# design.net
KiCad netlist of a schematic drawn in EasyEDA Pro
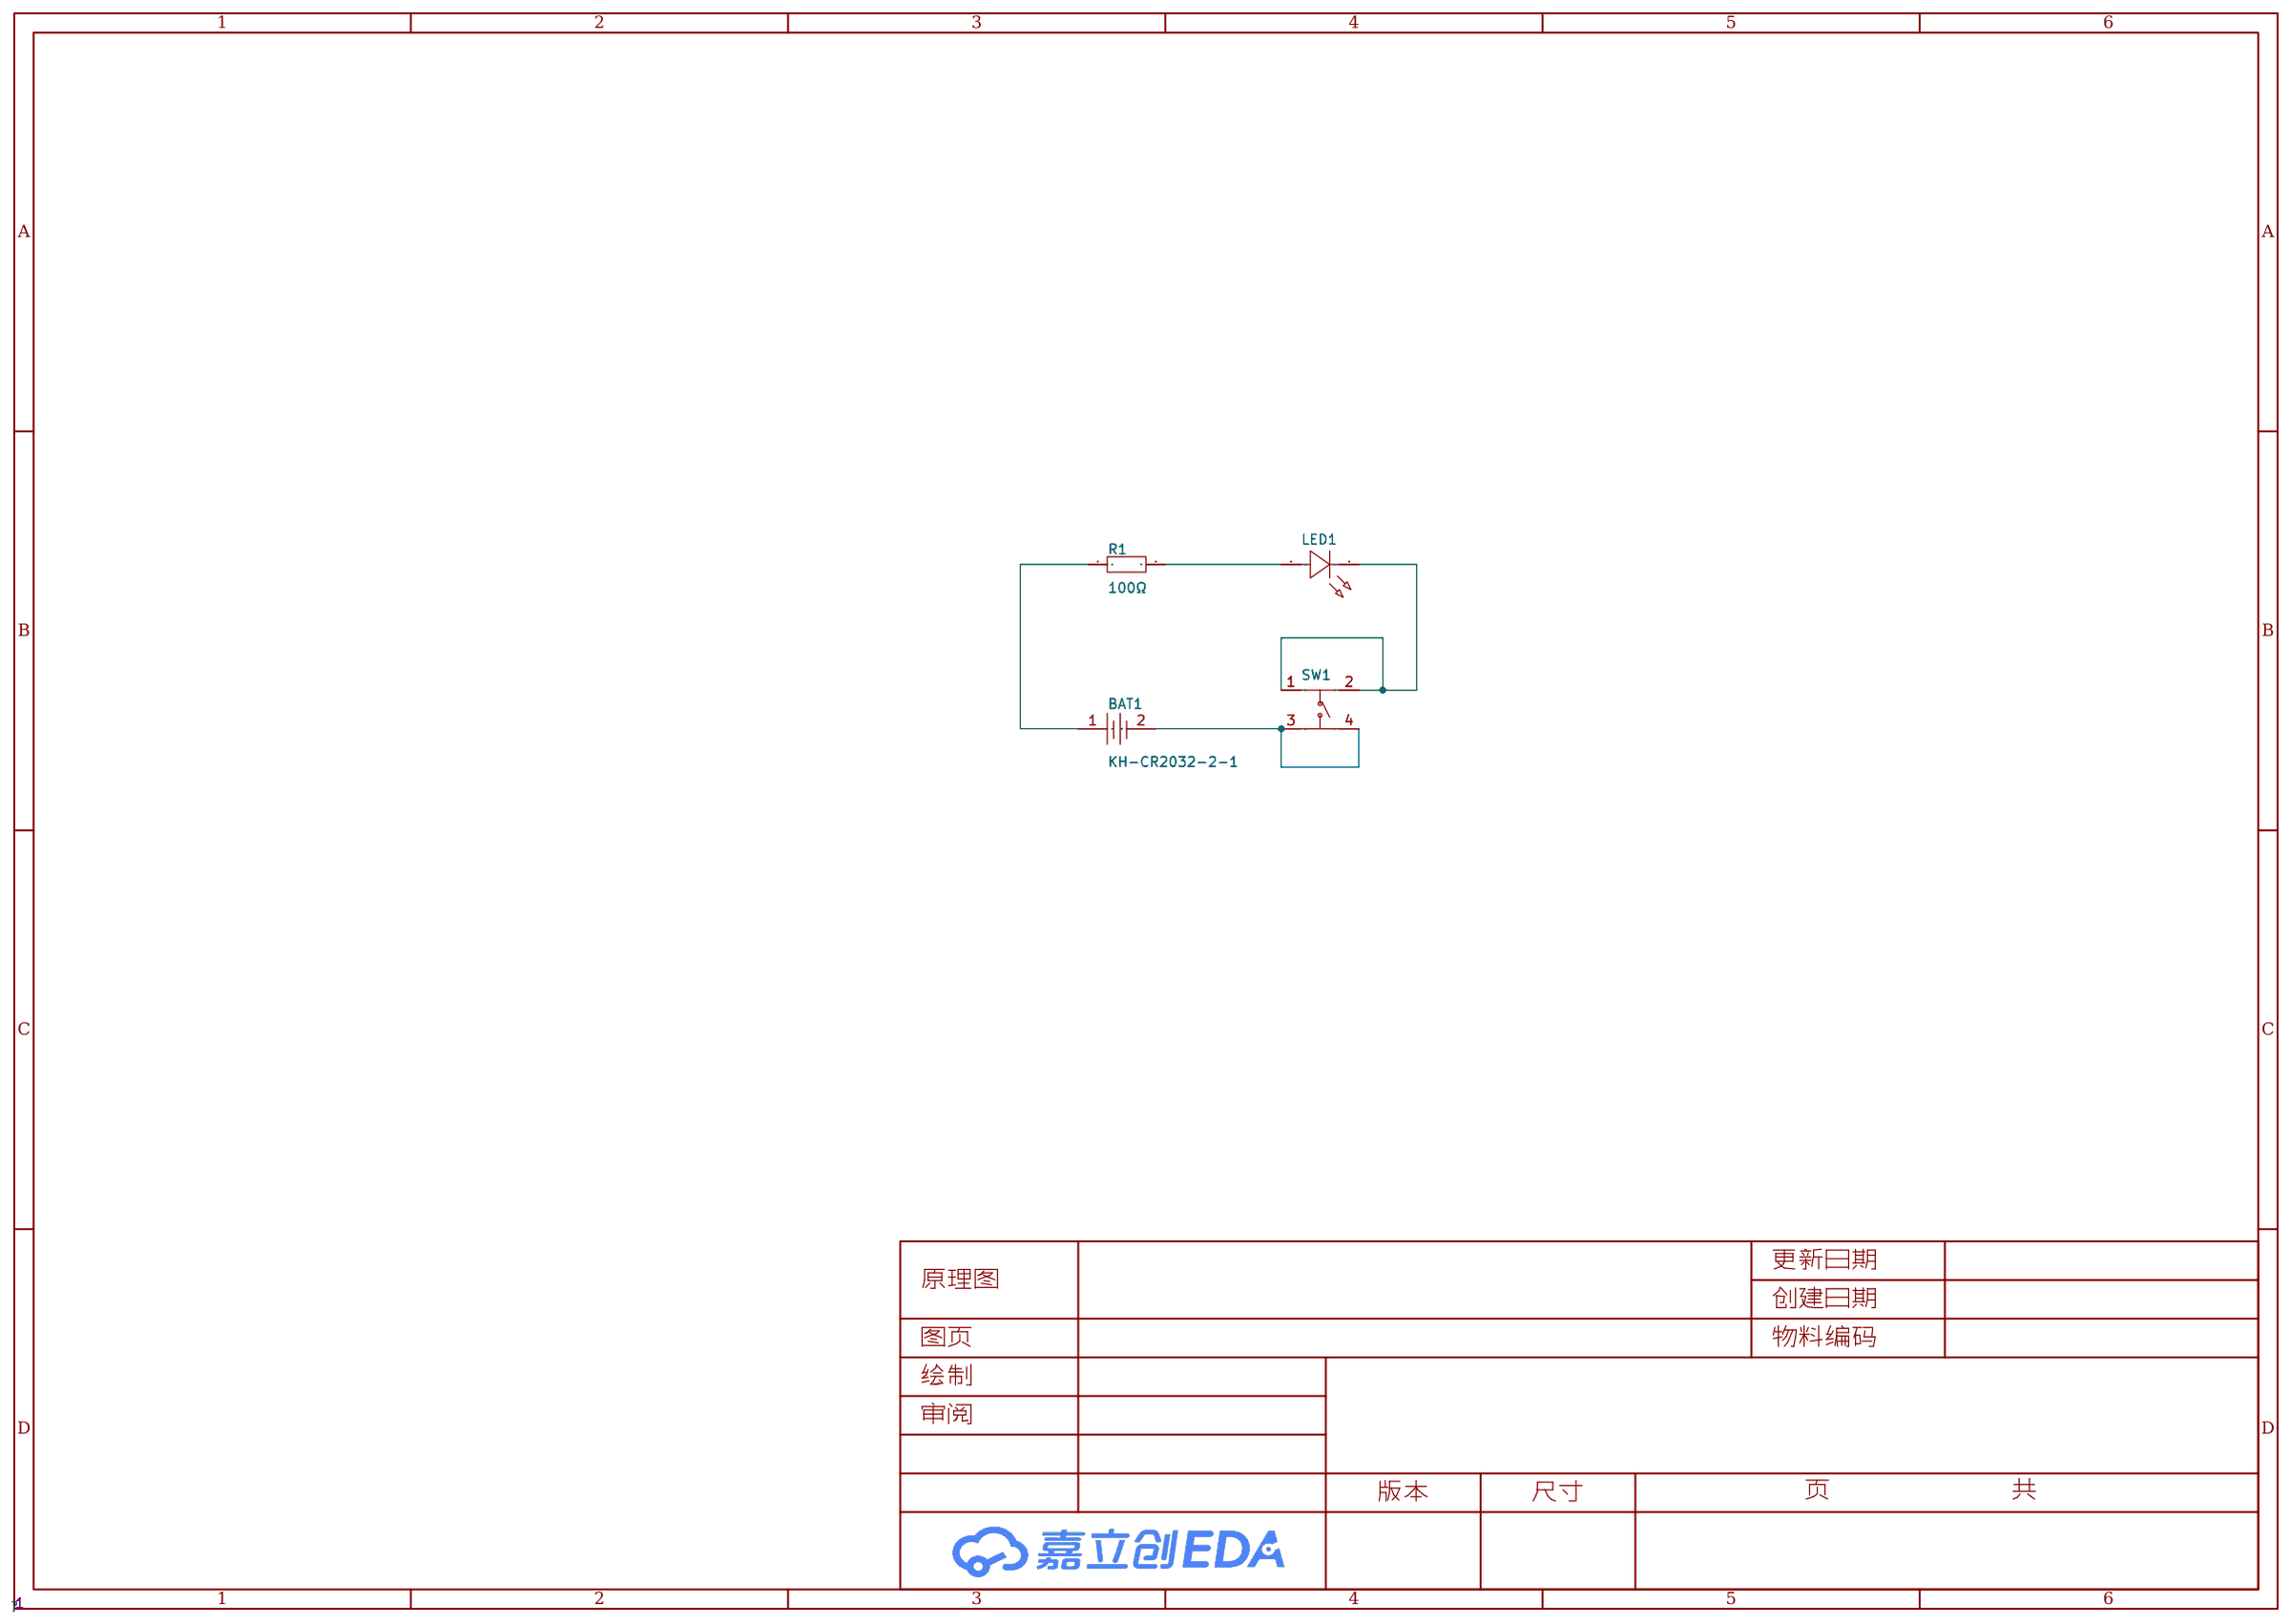
[diagram p0: schematic sheet]

(export (version "E")
  (design (tool "Eeschema 10.0.6"))
  (components
    (comp (ref "BAT1")
      (value "KH-CR2032-2-1")
      (footprint "easyedapro:BAT-TH_KH-CR2032-2-1")
      (description "B-2-1环保1号模 铜(加强版)")
      (fields (field (name "Manufacturer") "kinghelm(金航标)"))
      (libsource (lib "easyedapro") (part "KH-CR2032-2-1"))
    )
    (comp (ref "LED1")
      (value "264-10SURD/S530-A3")
      (footprint "easyedapro:LED-TH_BD3.2-P2.54-RD")
      (description "发光颜色:红色;正向电压(VF):2V;正向电流:20mA;主波长:624nm;透镜颜色:红色透镜;发光强度:125mcd;发光角度:60°;")
      (fields (field (name "Manufacturer") "EVERLIGHT(亿光)"))
      (libsource (lib "easyedapro") (part "264-10surd/s530-a3"))
    )
    (comp (ref "R1")
      (value "100Ω")
      (footprint "easyedapro:RES-TH_BD2.2-L6.5-P10.50-D0.6")
      (description "电阻类型:金属膜电阻;阻值:100Ω;精度:±1%;功率:250mW;温度系数:±50ppm/°C;")
      (fields
        (field (name "Manufacturer Part") "MFR0W4F1000A50")
        (field (name "Manufacturer") "UNI-ROYAL(厚声)")
      )
      (libsource (lib "easyedapro") (part "MFR0W4F1000A50"))
    )
    (comp (ref "SW1")
      (value "KH-6X6X5H-STM")
      (footprint "easyedapro:SW-SMD_4P-L6.0-W6.0-P4.50-LS9.0-2")
      (description "电路结构:单刀单掷;按钮形状:圆形按钮;安装方式:立贴;开关长度:6mm;开关宽度:6mm;开关高度:5mm;带支架:不带;触点电流:50mA;额定电压(DC):12V;机械寿命:8万次;")
      (fields (field (name "Manufacturer") "kinghelm(金航标)"))
      (libsource (lib "easyedapro") (part "KH-6X6X5H-STM"))
    )
  )
  (nets
    (net (code "1") (name "Net-(BAT1-Pad1)") (class "Default")
      (node (ref "BAT1") (pin "1") (pinfunction "1_1") (pintype "input"))
      (node (ref "R1") (pin "1") (pinfunction "1_1") (pintype "input"))
    )
    (net (code "2") (name "Net-(BAT1-Pad2)") (class "Default")
      (node (ref "BAT1") (pin "2") (pinfunction "2_2") (pintype "input"))
      (node (ref "SW1") (pin "3") (pinfunction "3_3") (pintype "unspecified"))
      (node (ref "SW1") (pin "4") (pinfunction "4_4") (pintype "unspecified"))
    )
    (net (code "3") (name "Net-(LED1-A)") (class "Default")
      (node (ref "LED1") (pin "2") (pinfunction "A_2") (pintype "unspecified"))
      (node (ref "R1") (pin "2") (pinfunction "2_2") (pintype "input"))
    )
    (net (code "4") (name "Net-(LED1-K)") (class "Default")
      (node (ref "LED1") (pin "1") (pinfunction "K_1") (pintype "unspecified"))
      (node (ref "SW1") (pin "1") (pinfunction "1_1") (pintype "unspecified"))
      (node (ref "SW1") (pin "2") (pinfunction "2_2") (pintype "unspecified"))
    )
  )
)
